# Power.net
KiCad netlist of a schematic drawn in Altium Designer
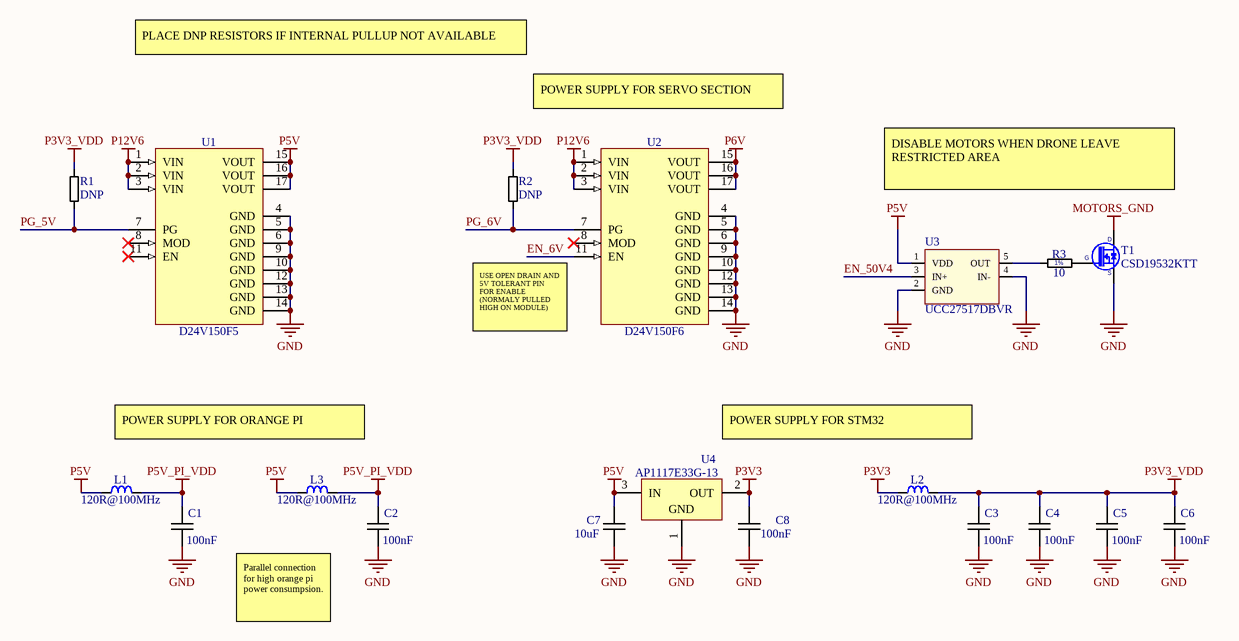
[diagram p0: Power.SchDoc]

(export (version "E")
  (design (tool "Eeschema 10.0.6"))
  (components
    (comp (ref "C1")
      (value "100nF")
      (footprint "CAPC0603X90N")
      (description "Non-polarised capacitor")
      (fields
        (field (name "MANUFACTURER") "GENERIC")
        (field (name "MANUFACTURER PART NUMBER") "CC0603_100NF_16V_10%_X7R")
        (field (name "AUTHOR") "KB")
      )
      (libsource (lib "Capacitors") (part "Capacitor - non polarized"))
    )
    (comp (ref "C2")
      (value "100nF")
      (footprint "CAPC0603X90N")
      (description "Non-polarised capacitor")
      (fields
        (field (name "MANUFACTURER") "GENERIC")
        (field (name "MANUFACTURER PART NUMBER") "CC0603_100NF_16V_10%_X7R")
        (field (name "AUTHOR") "KB")
      )
      (libsource (lib "Capacitors") (part "Capacitor - non polarized"))
    )
    (comp (ref "C3")
      (value "100nF")
      (footprint "CAPC0603X90N")
      (description "Non-polarised capacitor")
      (fields
        (field (name "MANUFACTURER") "GENERIC")
        (field (name "MANUFACTURER PART NUMBER") "CC0603_100NF_16V_10%_X7R")
        (field (name "AUTHOR") "KB")
      )
      (libsource (lib "Capacitors") (part "Capacitor - non polarized"))
    )
    (comp (ref "C4")
      (value "100nF")
      (footprint "CAPC0603X90N")
      (description "Non-polarised capacitor")
      (fields
        (field (name "MANUFACTURER") "GENERIC")
        (field (name "MANUFACTURER PART NUMBER") "CC0603_100NF_16V_10%_X7R")
        (field (name "AUTHOR") "KB")
      )
      (libsource (lib "Capacitors") (part "Capacitor - non polarized"))
    )
    (comp (ref "C5")
      (value "100nF")
      (footprint "CAPC0603X90N")
      (description "Non-polarised capacitor")
      (fields
        (field (name "MANUFACTURER") "GENERIC")
        (field (name "MANUFACTURER PART NUMBER") "CC0603_100NF_16V_10%_X7R")
        (field (name "AUTHOR") "KB")
      )
      (libsource (lib "Capacitors") (part "Capacitor - non polarized"))
    )
    (comp (ref "C6")
      (value "100nF")
      (footprint "CAPC0603X90N")
      (description "Non-polarised capacitor")
      (fields
        (field (name "MANUFACTURER") "GENERIC")
        (field (name "MANUFACTURER PART NUMBER") "CC0603_100NF_16V_10%_X7R")
        (field (name "AUTHOR") "KB")
      )
      (libsource (lib "Capacitors") (part "Capacitor - non polarized"))
    )
    (comp (ref "C7")
      (value "10uF")
      (footprint "CAPC0603X90N")
      (description "Non-polarised capacitor")
      (fields
        (field (name "MANUFACTURER") "GENERIC")
        (field (name "MANUFACTURER PART NUMBER") "CC0603_10UF_16V_20%_X5R")
        (field (name "AUTHOR") "KB")
      )
      (libsource (lib "Capacitors") (part "Capacitor - non polarized"))
    )
    (comp (ref "C8")
      (value "100nF")
      (footprint "CAPC0603X90N")
      (description "Non-polarised capacitor")
      (fields
        (field (name "MANUFACTURER") "GENERIC")
        (field (name "MANUFACTURER PART NUMBER") "CC0603_100NF_16V_10%_X7R")
        (field (name "AUTHOR") "KB")
      )
      (libsource (lib "Capacitors") (part "Capacitor - non polarized"))
    )
    (comp (ref "L1")
      (value "120R@100MHz")
      (footprint "INDC0603X90N")
      (description "Ferrite Bead")
      (fields
        (field (name "MANUFACTURER") "GENERIC")
        (field (name "MANUFACTURER PART NUMBER") "FB0603_120R@100MHZ_2A")
        (field (name "AUTHOR") "KB")
      )
      (libsource (lib "Inductors") (part "Inductor"))
    )
    (comp (ref "L2")
      (value "120R@100MHz")
      (footprint "INDC0603X90N")
      (description "Ferrite Bead")
      (fields
        (field (name "MANUFACTURER") "GENERIC")
        (field (name "MANUFACTURER PART NUMBER") "FB0603_120R@100MHZ_2A")
        (field (name "AUTHOR") "KB")
      )
      (libsource (lib "Inductors") (part "Inductor"))
    )
    (comp (ref "L3")
      (value "120R@100MHz")
      (footprint "INDC0603X90N")
      (description "Ferrite Bead")
      (fields
        (field (name "MANUFACTURER") "GENERIC")
        (field (name "MANUFACTURER PART NUMBER") "FB0603_120R@100MHZ_2A")
        (field (name "AUTHOR") "KB")
      )
      (libsource (lib "Inductors") (part "Inductor"))
    )
    (comp (ref "R1")
      (value "DNP")
      (footprint "RESC0603X60N")
      (description "General Purpose Thick Film Chip Resistor")
      (fields
        (field (name "MANUFACTURER") "GENERIC")
        (field (name "VOLTAGE") "75V")
        (field (name "AUTHOR") "KB")
      )
      (libsource (lib "Resistors") (part "Resistor - Generic"))
    )
    (comp (ref "R2")
      (value "DNP")
      (footprint "RESC0603X60N")
      (description "General Purpose Thick Film Chip Resistor")
      (fields
        (field (name "MANUFACTURER") "GENERIC")
        (field (name "VOLTAGE") "75V")
        (field (name "AUTHOR") "KB")
      )
      (libsource (lib "Resistors") (part "Resistor - Generic"))
    )
    (comp (ref "R3")
      (value "10")
      (footprint "RESC0603X60N")
      (description "General Purpose Thick Film Chip Resistor")
      (fields
        (field (name "MANUFACTURER") "GENERIC")
        (field (name "MANUFACTURER PART NUMBER") "R0603_10R0_0.0625W 0.1W 0.125W 0.25W 0.5W 1W 0.75W 1W_100PPM")
        (field (name "AUTHOR") "KB")
      )
      (libsource (lib "Resistors") (part "Resistor - 1%"))
    )
    (comp (ref "T1")
      (value "CSD19532KTT")
      (footprint "TO263-2")
      (description "N-MOS 100V 98A 4.6mOhm")
      (fields (field (name "AUTHOR") "PC"))
      (libsource (lib "ICs And Semiconductors") (part "N-MOSFET-D 1G 2S 3D"))
    )
    (comp (ref "U1")
      (value "D24V150F5")
      (footprint "D24V150Fx")
      (description "DC-DC Step-Down, IN: 6...40V, OUT: 5V")
      (fields (field (name "AUTHOR") "PC"))
      (libsource (lib "ICs And Semiconductors") (part "D24V150Fx"))
    )
    (comp (ref "U2")
      (value "D24V150F6")
      (footprint "D24V150Fx")
      (description "DC-DC Step-Down, IN: 7.2...40V, OUT: 6V")
      (fields (field (name "AUTHOR") "PC"))
      (libsource (lib "ICs And Semiconductors") (part "D24V150Fx"))
    )
    (comp (ref "U3")
      (value "UCC27517DBVR")
      (footprint "SOT23-5")
      (description "FET Single Gate Driver IC")
      (fields (field (name "AUTHOR") "BS"))
      (libsource (lib "ICs And Semiconductors") (part "UCC27517DBVR"))
    )
    (comp (ref "U4")
      (value "AP1117E33G-13")
      (footprint "SOT223")
      (description "1A Low dropout positive P3V3 regulator")
      (fields (field (name "AUTHOR") "JK"))
      (libsource (lib "ICs And Semiconductors") (part "REG3 1GND-2OUT-3IN"))
    )
  )
  (nets
    (net (code "1") (name "/EN_6V") (class "Default")
      (node (ref "U2") (pin "11") (pinfunction "EN_11") (pintype "input"))
    )
    (net (code "2") (name "/EN_50V4") (class "Default")
      (node (ref "U3") (pin "3") (pinfunction "IN+_3") (pintype "passive"))
    )
    (net (code "3") (name "/PG_5V") (class "Default")
      (node (ref "R1") (pin "1") (pinfunction "1_1") (pintype "passive"))
      (node (ref "U1") (pin "7") (pinfunction "PG_7") (pintype "open_collector"))
    )
    (net (code "4") (name "/PG_6V") (class "Default")
      (node (ref "R2") (pin "1") (pinfunction "1_1") (pintype "passive"))
      (node (ref "U2") (pin "7") (pinfunction "PG_7") (pintype "open_collector"))
    )
    (net (code "5") (name "GND") (class "Default")
      (node (ref "C1") (pin "1") (pinfunction "1_1") (pintype "passive"))
      (node (ref "C2") (pin "1") (pinfunction "1_1") (pintype "passive"))
      (node (ref "C3") (pin "1") (pinfunction "1_1") (pintype "passive"))
      (node (ref "C4") (pin "1") (pinfunction "1_1") (pintype "passive"))
      (node (ref "C5") (pin "1") (pinfunction "1_1") (pintype "passive"))
      (node (ref "C6") (pin "1") (pinfunction "1_1") (pintype "passive"))
      (node (ref "C7") (pin "1") (pinfunction "1_1") (pintype "passive"))
      (node (ref "C8") (pin "1") (pinfunction "1_1") (pintype "passive"))
      (node (ref "T1") (pin "2") (pinfunction "S_2") (pintype "passive"))
      (node (ref "U1") (pin "10") (pinfunction "GND_10") (pintype "power_in"))
      (node (ref "U1") (pin "12") (pinfunction "GND_12") (pintype "power_in"))
      (node (ref "U1") (pin "13") (pinfunction "GND_13") (pintype "power_in"))
      (node (ref "U1") (pin "14") (pinfunction "GND_14") (pintype "power_in"))
      (node (ref "U1") (pin "4") (pinfunction "GND_4") (pintype "power_in"))
      (node (ref "U1") (pin "5") (pinfunction "GND_5") (pintype "power_in"))
      (node (ref "U1") (pin "6") (pinfunction "GND_6") (pintype "power_in"))
      (node (ref "U1") (pin "9") (pinfunction "GND_9") (pintype "power_in"))
      (node (ref "U2") (pin "10") (pinfunction "GND_10") (pintype "power_in"))
      (node (ref "U2") (pin "12") (pinfunction "GND_12") (pintype "power_in"))
      (node (ref "U2") (pin "13") (pinfunction "GND_13") (pintype "power_in"))
      (node (ref "U2") (pin "14") (pinfunction "GND_14") (pintype "power_in"))
      (node (ref "U2") (pin "4") (pinfunction "GND_4") (pintype "power_in"))
      (node (ref "U2") (pin "5") (pinfunction "GND_5") (pintype "power_in"))
      (node (ref "U2") (pin "6") (pinfunction "GND_6") (pintype "power_in"))
      (node (ref "U2") (pin "9") (pinfunction "GND_9") (pintype "power_in"))
      (node (ref "U3") (pin "2") (pinfunction "GND_2") (pintype "passive"))
      (node (ref "U3") (pin "4") (pinfunction "IN-_4") (pintype "passive"))
      (node (ref "U4") (pin "1") (pinfunction "GND_1") (pintype "power_in"))
    )
    (net (code "6") (name "MOTORS_GND") (class "Default")
      (node (ref "T1") (pin "3") (pinfunction "D_3") (pintype "passive"))
    )
    (net (code "7") (name "Net-(T1-G)") (class "Default")
      (node (ref "R3") (pin "2") (pinfunction "2_2") (pintype "passive"))
      (node (ref "T1") (pin "1") (pinfunction "G_1") (pintype "passive"))
    )
    (net (code "8") (name "Net-(U3-OUT)") (class "Default")
      (node (ref "R3") (pin "1") (pinfunction "1_1") (pintype "passive"))
      (node (ref "U3") (pin "5") (pinfunction "OUT_5") (pintype "passive"))
    )
    (net (code "9") (name "P3V3") (class "Default")
      (node (ref "C8") (pin "2") (pinfunction "2_2") (pintype "passive"))
      (node (ref "L2") (pin "1") (pinfunction "1_1") (pintype "passive"))
      (node (ref "U4") (pin "2") (pinfunction "OUT_2") (pintype "power_in"))
    )
    (net (code "10") (name "P3V3_VDD") (class "Default")
      (node (ref "C3") (pin "2") (pinfunction "2_2") (pintype "passive"))
      (node (ref "C4") (pin "2") (pinfunction "2_2") (pintype "passive"))
      (node (ref "C5") (pin "2") (pinfunction "2_2") (pintype "passive"))
      (node (ref "C6") (pin "2") (pinfunction "2_2") (pintype "passive"))
      (node (ref "L2") (pin "2") (pinfunction "2_2") (pintype "passive"))
      (node (ref "R1") (pin "2") (pinfunction "2_2") (pintype "passive"))
      (node (ref "R2") (pin "2") (pinfunction "2_2") (pintype "passive"))
    )
    (net (code "11") (name "P5V") (class "Default")
      (node (ref "C7") (pin "2") (pinfunction "2_2") (pintype "passive"))
      (node (ref "L1") (pin "1") (pinfunction "1_1") (pintype "passive"))
      (node (ref "L3") (pin "1") (pinfunction "1_1") (pintype "passive"))
      (node (ref "U1") (pin "15") (pinfunction "VOUT_15") (pintype "power_in"))
      (node (ref "U1") (pin "16") (pinfunction "VOUT_16") (pintype "power_in"))
      (node (ref "U1") (pin "17") (pinfunction "VOUT_17") (pintype "power_in"))
      (node (ref "U3") (pin "1") (pinfunction "VDD_1") (pintype "passive"))
      (node (ref "U4") (pin "3") (pinfunction "IN_3") (pintype "power_in"))
    )
    (net (code "12") (name "P5V_PI_VDD") (class "Default")
      (node (ref "C1") (pin "2") (pinfunction "2_2") (pintype "passive"))
      (node (ref "C2") (pin "2") (pinfunction "2_2") (pintype "passive"))
      (node (ref "L1") (pin "2") (pinfunction "2_2") (pintype "passive"))
      (node (ref "L3") (pin "2") (pinfunction "2_2") (pintype "passive"))
    )
    (net (code "13") (name "P6V") (class "Default")
      (node (ref "U2") (pin "15") (pinfunction "VOUT_15") (pintype "power_in"))
      (node (ref "U2") (pin "16") (pinfunction "VOUT_16") (pintype "power_in"))
      (node (ref "U2") (pin "17") (pinfunction "VOUT_17") (pintype "power_in"))
    )
    (net (code "14") (name "P12V6") (class "Default")
      (node (ref "U1") (pin "1") (pinfunction "VIN_1") (pintype "input"))
      (node (ref "U1") (pin "2") (pinfunction "VIN_2") (pintype "input"))
      (node (ref "U1") (pin "3") (pinfunction "VIN_3") (pintype "input"))
      (node (ref "U2") (pin "1") (pinfunction "VIN_1") (pintype "input"))
      (node (ref "U2") (pin "2") (pinfunction "VIN_2") (pintype "input"))
      (node (ref "U2") (pin "3") (pinfunction "VIN_3") (pintype "input"))
    )
    (net (code "15") (name "unconnected-(U1-EN-Pad11)") (class "Default")
      (node (ref "U1") (pin "11") (pinfunction "EN_11") (pintype "input+no_connect"))
    )
    (net (code "16") (name "unconnected-(U1-MOD-Pad8)") (class "Default")
      (node (ref "U1") (pin "8") (pinfunction "MOD_8") (pintype "input+no_connect"))
    )
    (net (code "17") (name "unconnected-(U2-MOD-Pad8)") (class "Default")
      (node (ref "U2") (pin "8") (pinfunction "MOD_8") (pintype "input+no_connect"))
    )
  )
)
